# two_ch.net
KiCad netlist of a schematic drawn in Altium Designer
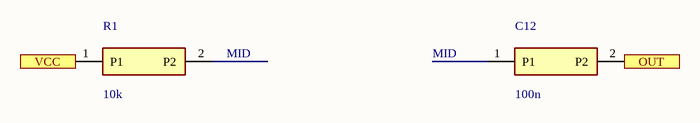
[diagram p0: two_ch.SchDoc]

(export (version "E")
  (design (tool "Eeschema 10.0.6"))
  (components
    (comp (ref "C12") (value "100n") (libsource (lib "FenoliteChannels") (part "CAP")))
    (comp (ref "R1") (value "10k") (libsource (lib "FenoliteChannels") (part "RES")))
  )
  (nets
    (net (code "1") (name "/MID") (class "Default")
      (node (ref "C12") (pin "1") (pinfunction "P1_1") (pintype "passive"))
      (node (ref "R1") (pin "2") (pinfunction "P2_2") (pintype "passive"))
    )
    (net (code "2") (name "/OUT") (class "Default")
      (node (ref "C12") (pin "2") (pinfunction "P2_2") (pintype "passive"))
    )
    (net (code "3") (name "/VCC") (class "Default")
      (node (ref "R1") (pin "1") (pinfunction "P1_1") (pintype "passive"))
    )
  )
)
